# ESP32-S3.net
KiCad netlist of a schematic drawn in Altium Designer
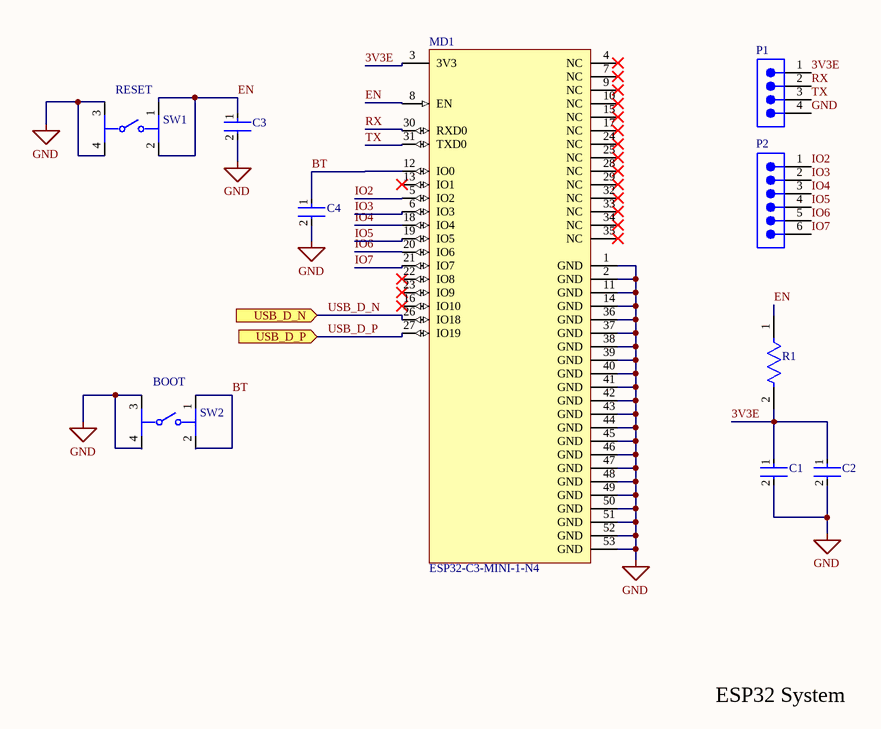
[diagram p0: ESP32-S3.SchDoc]

(export (version "E")
  (design (tool "Eeschema 10.0.6"))
  (components
    (comp (ref "C1")
      (value "HMK105B7103MVHFE")
      (footprint "FP-0402-L_1_0_0_05-W_0_5-IPC_A")
      (description "None")
      (libsource (lib "Altium Content Vault") (part "b4654b650e69147ec39a6b967a45e02"))
    )
    (comp (ref "C2")
      (value "LMK316AB7106ML-T")
      (footprint "FP-1206-L_3_2_0_2-W_1_6_0-IPC_A")
      (description "None")
      (fields (field (name "VOLTAGE") "10V") (field (name "TOLERANCE") "20%"))
      (libsource (lib "Altium Content Vault") (part "b4654b650e69147ec39a6b967a45e02"))
    )
    (comp (ref "C3")
      (value "HMK105B7103MVHFE")
      (footprint "FP-0402-L_1_0_0_05-W_0_5-IPC_A")
      (description "None")
      (libsource (lib "Altium Content Vault") (part "b4654b650e69147ec39a6b967a45e02"))
    )
    (comp (ref "C4")
      (value "HMK105B7103MVHFE")
      (footprint "FP-0402-L_1_0_0_05-W_0_5-IPC_A")
      (description "None")
      (libsource (lib "Altium Content Vault") (part "b4654b650e69147ec39a6b967a45e02"))
    )
    (comp (ref "MD1")
      (value "ESP32-C3-MINI-1-N4")
      (footprint "FP-ESP32-C3-MINI-1-N4-MFG")
      (description "Multiprotocol Modules SMD module, ESP32-C3FN4, PCB antenna, -40 C +85 C")
      (libsource (lib "Altium Content Vault") (part "ESP32-C3-MINI-1-N4"))
    )
    (comp (ref "P1")
      (value "TSW-104-08-G-S")
      (footprint "SMTC-TSW-104-08-X-S")
      (description "0.025\" SQ Post Header, Through-hole, Vertical, -55 to 125 degC, 2.54 mm Pitch, 4-Pin, Male, RoHS")
      (fields (field (name "MANUFACTURER") "Samtec"))
      (libsource (lib "Altium Content Vault") (part "SMTC-TSW-104-08-X-S"))
    )
    (comp (ref "P2")
      (value "TSW-106-23-G-S")
      (footprint "SMTC-TSW-106-23-X-S")
      (description "0.025\" SQ Post Header, Through-hole, Vertical, -55 to 125 degC, 2.54 mm Pitch, 6-Pin, Male, RoHS")
      (fields (field (name "MANUFACTURER") "Samtec"))
      (libsource (lib "Altium Content Vault") (part "SMTC-TSW-106-X-X-S-X"))
    )
    (comp (ref "R1")
      (value "CR2010-JW-103ELF")
      (footprint "FP-CR2010-IPC_C")
      (description "Thick Film Chip Resistors 2010 10kΩ 0.5W 5% 200ppm/°C")
      (fields (field (name "TOLERANCE") "5%"))
      (libsource (lib "Altium Content Vault") (part "1029c3af85768c4190bb7ad29bc67b5"))
    )
    (comp (ref "SW1")
      (value "RESET")
      (footprint "FP-PTS647SM38SMTR2LFS-MFG")
      (description "TACT 4.5 X 4.5, 3.8 MM H, 1.8N,")
      (libsource (lib "Altium Content Vault") (part "1adf0dd01260c80cf25a44bfd6b99ba"))
    )
    (comp (ref "SW2")
      (value "BOOT")
      (footprint "FP-PTS647SM38SMTR2LFS-MFG")
      (description "TACT 4.5 X 4.5, 3.8 MM H, 1.8N,")
      (libsource (lib "Altium Content Vault") (part "1adf0dd01260c80cf25a44bfd6b99ba"))
    )
  )
  (nets
    (net (code "1") (name "/3V3E") (class "Default")
      (node (ref "C1") (pin "1") (pinfunction "1_1") (pintype "passive"))
      (node (ref "C2") (pin "1") (pinfunction "1_1") (pintype "passive"))
      (node (ref "MD1") (pin "3") (pinfunction "3V3_3") (pintype "power_in"))
      (node (ref "P1") (pin "1") (pinfunction "1_1") (pintype "passive"))
      (node (ref "R1") (pin "2") (pinfunction "2_2") (pintype "passive"))
    )
    (net (code "3") (name "/BT") (class "Default")
      (node (ref "C4") (pin "1") (pinfunction "1_1") (pintype "passive"))
      (node (ref "MD1") (pin "12") (pinfunction "IO0_12") (pintype "bidirectional"))
      (node (ref "SW2") (pin "1") (pinfunction "1_1") (pintype "passive"))
      (node (ref "SW2") (pin "2") (pinfunction "2_2") (pintype "passive"))
    )
    (net (code "4") (name "/EN") (class "Default")
      (node (ref "C3") (pin "1") (pinfunction "1_1") (pintype "passive"))
      (node (ref "MD1") (pin "8") (pinfunction "EN_8") (pintype "input"))
      (node (ref "R1") (pin "1") (pinfunction "1_1") (pintype "passive"))
      (node (ref "SW1") (pin "1") (pinfunction "1_1") (pintype "passive"))
      (node (ref "SW1") (pin "2") (pinfunction "2_2") (pintype "passive"))
    )
    (net (code "5") (name "/IO2") (class "Default")
      (node (ref "MD1") (pin "5") (pinfunction "IO2_5") (pintype "bidirectional"))
      (node (ref "P2") (pin "1") (pinfunction "1_1") (pintype "passive"))
    )
    (net (code "6") (name "/IO3") (class "Default")
      (node (ref "MD1") (pin "6") (pinfunction "IO3_6") (pintype "bidirectional"))
      (node (ref "P2") (pin "2") (pinfunction "2_2") (pintype "passive"))
    )
    (net (code "7") (name "/IO4") (class "Default")
      (node (ref "MD1") (pin "18") (pinfunction "IO4_18") (pintype "bidirectional"))
      (node (ref "P2") (pin "3") (pinfunction "3_3") (pintype "passive"))
    )
    (net (code "8") (name "/IO5") (class "Default")
      (node (ref "MD1") (pin "19") (pinfunction "IO5_19") (pintype "bidirectional"))
      (node (ref "P2") (pin "4") (pinfunction "4_4") (pintype "passive"))
    )
    (net (code "9") (name "/IO6") (class "Default")
      (node (ref "MD1") (pin "20") (pinfunction "IO6_20") (pintype "bidirectional"))
      (node (ref "P2") (pin "5") (pinfunction "5_5") (pintype "passive"))
    )
    (net (code "10") (name "/IO7") (class "Default")
      (node (ref "MD1") (pin "21") (pinfunction "IO7_21") (pintype "bidirectional"))
      (node (ref "P2") (pin "6") (pinfunction "6_6") (pintype "passive"))
    )
    (net (code "11") (name "/RX") (class "Default")
      (node (ref "MD1") (pin "30") (pinfunction "RXD0_30") (pintype "bidirectional"))
      (node (ref "P1") (pin "2") (pinfunction "2_2") (pintype "passive"))
    )
    (net (code "12") (name "/TX") (class "Default")
      (node (ref "MD1") (pin "31") (pinfunction "TXD0_31") (pintype "bidirectional"))
      (node (ref "P1") (pin "3") (pinfunction "3_3") (pintype "passive"))
    )
    (net (code "13") (name "/USB_D_N") (class "Default")
      (node (ref "MD1") (pin "26") (pinfunction "IO18_26") (pintype "bidirectional"))
    )
    (net (code "14") (name "/USB_D_P") (class "Default")
      (node (ref "MD1") (pin "27") (pinfunction "IO19_27") (pintype "bidirectional"))
    )
    (net (code "15") (name "GND") (class "Default")
      (node (ref "C1") (pin "2") (pinfunction "2_2") (pintype "passive"))
      (node (ref "C2") (pin "2") (pinfunction "2_2") (pintype "passive"))
      (node (ref "C3") (pin "2") (pinfunction "2_2") (pintype "passive"))
      (node (ref "C4") (pin "2") (pinfunction "2_2") (pintype "passive"))
      (node (ref "MD1") (pin "1") (pinfunction "GND_1") (pintype "power_in"))
      (node (ref "MD1") (pin "11") (pinfunction "GND_11") (pintype "power_in"))
      (node (ref "MD1") (pin "14") (pinfunction "GND_14") (pintype "power_in"))
      (node (ref "MD1") (pin "2") (pinfunction "GND_2") (pintype "power_in"))
      (node (ref "MD1") (pin "36") (pinfunction "GND_36") (pintype "power_in"))
      (node (ref "MD1") (pin "37") (pinfunction "GND_37") (pintype "power_in"))
      (node (ref "MD1") (pin "38") (pinfunction "GND_38") (pintype "power_in"))
      (node (ref "MD1") (pin "39") (pinfunction "GND_39") (pintype "power_in"))
      (node (ref "MD1") (pin "40") (pinfunction "GND_40") (pintype "power_in"))
      (node (ref "MD1") (pin "41") (pinfunction "GND_41") (pintype "power_in"))
      (node (ref "MD1") (pin "42") (pinfunction "GND_42") (pintype "power_in"))
      (node (ref "MD1") (pin "43") (pinfunction "GND_43") (pintype "power_in"))
      (node (ref "MD1") (pin "44") (pinfunction "GND_44") (pintype "power_in"))
      (node (ref "MD1") (pin "45") (pinfunction "GND_45") (pintype "power_in"))
      (node (ref "MD1") (pin "46") (pinfunction "GND_46") (pintype "power_in"))
      (node (ref "MD1") (pin "47") (pinfunction "GND_47") (pintype "power_in"))
      (node (ref "MD1") (pin "48") (pinfunction "GND_48") (pintype "power_in"))
      (node (ref "MD1") (pin "49") (pinfunction "GND_49") (pintype "power_in"))
      (node (ref "MD1") (pin "50") (pinfunction "GND_50") (pintype "power_in"))
      (node (ref "MD1") (pin "51") (pinfunction "GND_51") (pintype "power_in"))
      (node (ref "MD1") (pin "52") (pinfunction "GND_52") (pintype "power_in"))
      (node (ref "MD1") (pin "53") (pinfunction "GND_53") (pintype "power_in"))
      (node (ref "P1") (pin "4") (pinfunction "4_4") (pintype "passive"))
      (node (ref "SW1") (pin "3") (pinfunction "3_3") (pintype "passive"))
      (node (ref "SW1") (pin "4") (pinfunction "4_4") (pintype "passive"))
      (node (ref "SW2") (pin "3") (pinfunction "3_3") (pintype "passive"))
      (node (ref "SW2") (pin "4") (pinfunction "4_4") (pintype "passive"))
    )
    (net (code "16") (name "unconnected-(MD1-IO1-Pad13)") (class "Default")
      (node (ref "MD1") (pin "13") (pinfunction "IO1_13") (pintype "bidirectional+no_connect"))
    )
    (net (code "17") (name "unconnected-(MD1-IO8-Pad22)") (class "Default")
      (node (ref "MD1") (pin "22") (pinfunction "IO8_22") (pintype "bidirectional+no_connect"))
    )
    (net (code "18") (name "unconnected-(MD1-IO9-Pad23)") (class "Default")
      (node (ref "MD1") (pin "23") (pinfunction "IO9_23") (pintype "bidirectional+no_connect"))
    )
    (net (code "19") (name "unconnected-(MD1-IO10-Pad16)") (class "Default")
      (node (ref "MD1") (pin "16") (pinfunction "IO10_16") (pintype "bidirectional+no_connect"))
    )
    (net (code "20") (name "unconnected-(MD1-NC-Pad4)") (class "Default")
      (node (ref "MD1") (pin "4") (pinfunction "NC_4") (pintype "passive+no_connect"))
    )
    (net (code "21") (name "unconnected-(MD1-NC-Pad7)") (class "Default")
      (node (ref "MD1") (pin "7") (pinfunction "NC_7") (pintype "passive+no_connect"))
    )
    (net (code "22") (name "unconnected-(MD1-NC-Pad9)") (class "Default")
      (node (ref "MD1") (pin "9") (pinfunction "NC_9") (pintype "passive+no_connect"))
    )
    (net (code "23") (name "unconnected-(MD1-NC-Pad10)") (class "Default")
      (node (ref "MD1") (pin "10") (pinfunction "NC_10") (pintype "passive+no_connect"))
    )
    (net (code "24") (name "unconnected-(MD1-NC-Pad15)") (class "Default")
      (node (ref "MD1") (pin "15") (pinfunction "NC_15") (pintype "passive+no_connect"))
    )
    (net (code "25") (name "unconnected-(MD1-NC-Pad17)") (class "Default")
      (node (ref "MD1") (pin "17") (pinfunction "NC_17") (pintype "passive+no_connect"))
    )
    (net (code "26") (name "unconnected-(MD1-NC-Pad24)") (class "Default")
      (node (ref "MD1") (pin "24") (pinfunction "NC_24") (pintype "passive+no_connect"))
    )
    (net (code "27") (name "unconnected-(MD1-NC-Pad25)") (class "Default")
      (node (ref "MD1") (pin "25") (pinfunction "NC_25") (pintype "passive+no_connect"))
    )
    (net (code "28") (name "unconnected-(MD1-NC-Pad28)") (class "Default")
      (node (ref "MD1") (pin "28") (pinfunction "NC_28") (pintype "passive+no_connect"))
    )
    (net (code "29") (name "unconnected-(MD1-NC-Pad29)") (class "Default")
      (node (ref "MD1") (pin "29") (pinfunction "NC_29") (pintype "passive+no_connect"))
    )
    (net (code "30") (name "unconnected-(MD1-NC-Pad32)") (class "Default")
      (node (ref "MD1") (pin "32") (pinfunction "NC_32") (pintype "passive+no_connect"))
    )
    (net (code "31") (name "unconnected-(MD1-NC-Pad33)") (class "Default")
      (node (ref "MD1") (pin "33") (pinfunction "NC_33") (pintype "passive+no_connect"))
    )
    (net (code "32") (name "unconnected-(MD1-NC-Pad34)") (class "Default")
      (node (ref "MD1") (pin "34") (pinfunction "NC_34") (pintype "passive+no_connect"))
    )
    (net (code "33") (name "unconnected-(MD1-NC-Pad35)") (class "Default")
      (node (ref "MD1") (pin "35") (pinfunction "NC_35") (pintype "passive+no_connect"))
    )
  )
)
